# DualMotorCape-v6.net
KiCad netlist of a schematic drawn in EAGLE
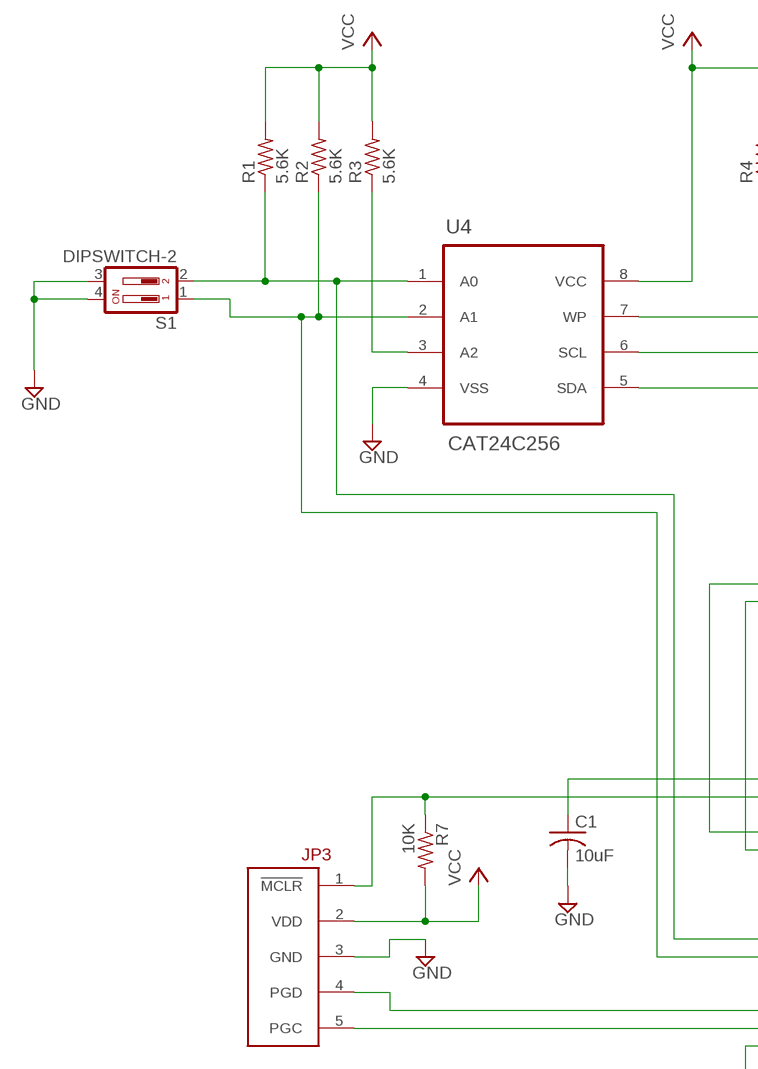
[diagram p0: schematic, sheet 1, part 1 of 2]
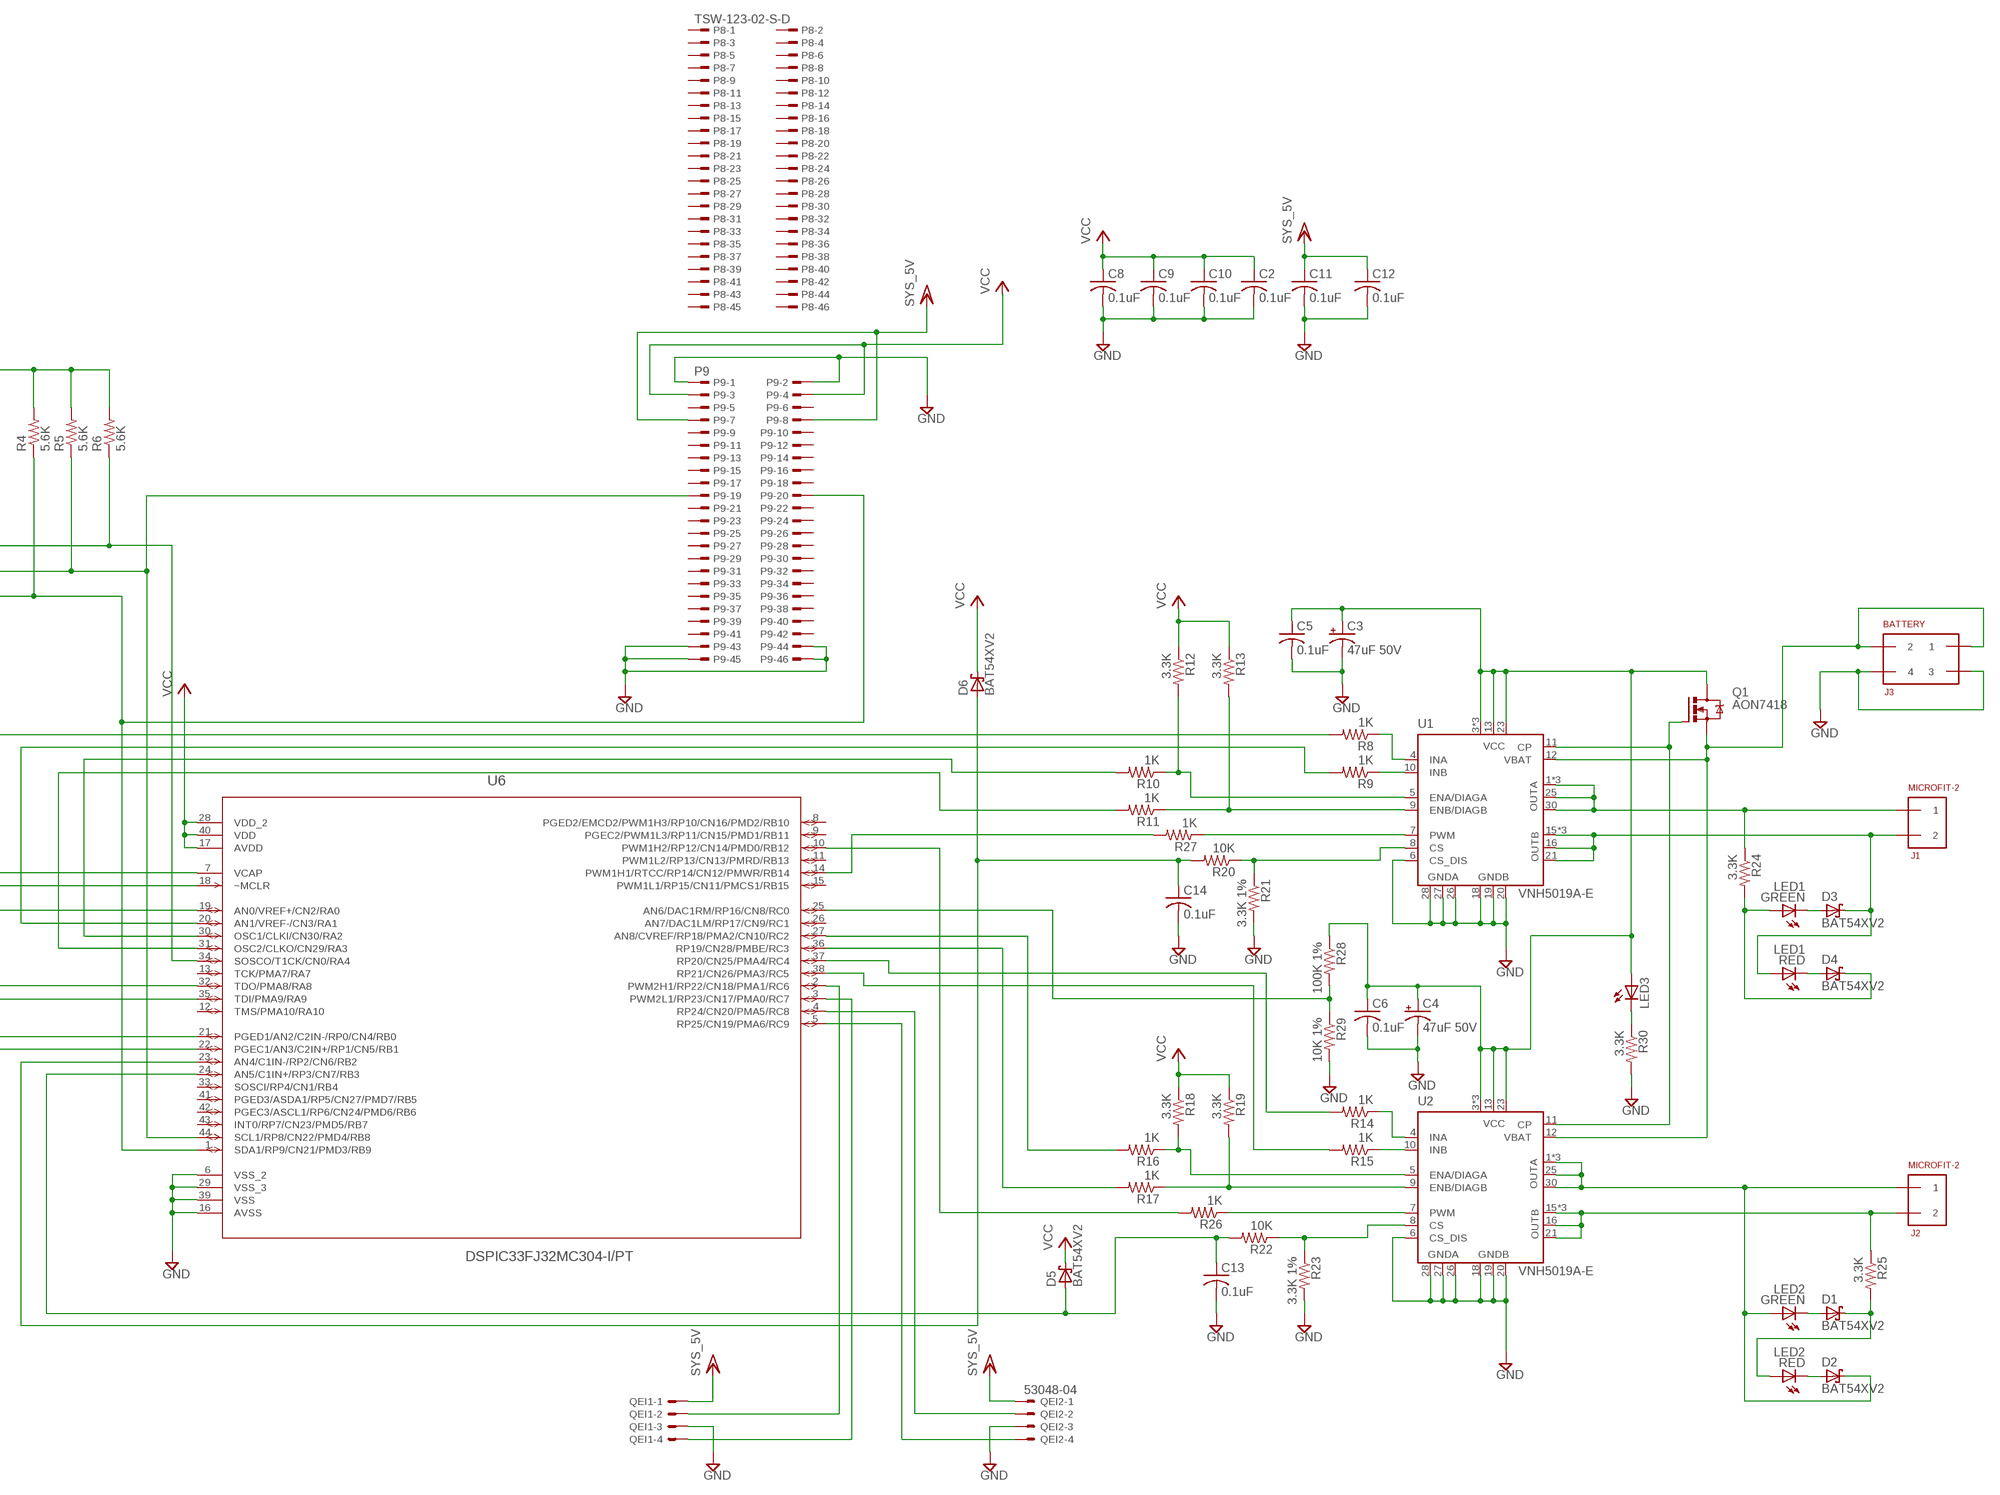
[diagram p1: schematic, sheet 1, part 2 of 2]

(export (version "E")
  (design (tool "Eeschema 10.0.6"))
  (components
    (comp (ref "C1")
      (value "10uF")
      (footprint "eagle-import:C0805")
      (libsource (lib "eagle-import") (part "C-USC0805"))
    )
    (comp (ref "C2")
      (value "0.1uF")
      (footprint "eagle-import:C0603")
      (libsource (lib "eagle-import") (part "C-USC0603"))
    )
    (comp (ref "C3")
      (value "47uF 50V")
      (footprint "eagle-import:UD-8X10_NICHICON")
      (libsource (lib "eagle-import") (part "CPOL-USUD-8X10"))
    )
    (comp (ref "C4")
      (value "47uF 50V")
      (footprint "eagle-import:UD-8X10_NICHICON")
      (libsource (lib "eagle-import") (part "CPOL-USUD-8X10"))
    )
    (comp (ref "C5")
      (value "0.1uF")
      (footprint "eagle-import:C0603")
      (libsource (lib "eagle-import") (part "C-USC0603"))
    )
    (comp (ref "C6")
      (value "0.1uF")
      (footprint "eagle-import:C0603")
      (libsource (lib "eagle-import") (part "C-USC0603"))
    )
    (comp (ref "C8")
      (value "0.1uF")
      (footprint "eagle-import:C0603")
      (libsource (lib "eagle-import") (part "C-USC0603"))
    )
    (comp (ref "C9")
      (value "0.1uF")
      (footprint "eagle-import:C0603")
      (libsource (lib "eagle-import") (part "C-USC0603"))
    )
    (comp (ref "C10")
      (value "0.1uF")
      (footprint "eagle-import:C0603")
      (libsource (lib "eagle-import") (part "C-USC0603"))
    )
    (comp (ref "C11")
      (value "0.1uF")
      (footprint "eagle-import:C0603")
      (libsource (lib "eagle-import") (part "C-USC0603"))
    )
    (comp (ref "C12")
      (value "0.1uF")
      (footprint "eagle-import:C0603")
      (libsource (lib "eagle-import") (part "C-USC0603"))
    )
    (comp (ref "C13")
      (value "0.1uF")
      (footprint "eagle-import:C0603")
      (libsource (lib "eagle-import") (part "C-USC0603"))
    )
    (comp (ref "C14")
      (value "0.1uF")
      (footprint "eagle-import:C0603")
      (libsource (lib "eagle-import") (part "C-USC0603"))
    )
    (comp (ref "D1")
      (value "BAT54XV2")
      (footprint "eagle-import:SOD523")
      (libsource (lib "eagle-import") (part "BAT54XV2"))
    )
    (comp (ref "D2")
      (value "BAT54XV2")
      (footprint "eagle-import:SOD523")
      (libsource (lib "eagle-import") (part "BAT54XV2"))
    )
    (comp (ref "D3")
      (value "BAT54XV2")
      (footprint "eagle-import:SOD523")
      (libsource (lib "eagle-import") (part "BAT54XV2"))
    )
    (comp (ref "D4")
      (value "BAT54XV2")
      (footprint "eagle-import:SOD523")
      (libsource (lib "eagle-import") (part "BAT54XV2"))
    )
    (comp (ref "D5")
      (value "BAT54XV2")
      (footprint "eagle-import:SOD523")
      (libsource (lib "eagle-import") (part "BAT54XV2"))
    )
    (comp (ref "D6")
      (value "BAT54XV2")
      (footprint "eagle-import:SOD523")
      (libsource (lib "eagle-import") (part "BAT54XV2"))
    )
    (comp (ref "J1")
      (value "MICROFIT-2")
      (footprint "eagle-import:MICROFIT-2-R-TH")
      (libsource (lib "eagle-import") (part "MICROFIT-2"))
    )
    (comp (ref "J2")
      (value "MICROFIT-2")
      (footprint "eagle-import:MICROFIT-2-R-TH")
      (libsource (lib "eagle-import") (part "MICROFIT-2"))
    )
    (comp (ref "J3")
      (value "BATTERY")
      (footprint "eagle-import:MICROFIT-4-R-TH")
      (libsource (lib "eagle-import") (part "MICROFIT-4"))
    )
    (comp (ref "JP3")
      (value "ICD2/3-HEADER")
      (footprint "eagle-import:ICD2_3-HEADER")
      (libsource (lib "eagle-import") (part "ICD2/3-HEADER"))
    )
    (comp (ref "LED1")
      (value "KINGBRIGHT-BI-COLOR-LED")
      (footprint "eagle-import:LED-1.6X1.5MM-BI-COLOR")
      (libsource (lib "eagle-import") (part "KINGBRIGHT-BI-COLOR-LED"))
    )
    (comp (ref "LED2")
      (value "KINGBRIGHT-BI-COLOR-LED")
      (footprint "eagle-import:LED-1.6X1.5MM-BI-COLOR")
      (libsource (lib "eagle-import") (part "KINGBRIGHT-BI-COLOR-LED"))
    )
    (comp (ref "LED3")
      (value "LED-LNJP12X8ARA")
      (footprint "eagle-import:LED-603-PANASONIC")
      (libsource (lib "eagle-import") (part "LED-LNJP12X8ARA"))
    )
    (comp (ref "P8")
      (value "TSW-123-02-S-D")
      (footprint "eagle-import:TSW-123-02-S-D")
      (libsource (lib "eagle-import") (part "TSW-123-02-S-D"))
    )
    (comp (ref "P9")
      (value "P9")
      (footprint "eagle-import:TSW-123-02-S-D")
      (libsource (lib "eagle-import") (part "TSW-123-02-S-D"))
    )
    (comp (ref "Q1")
      (value "AON7418")
      (footprint "eagle-import:DFN3.3X3.3")
      (libsource (lib "eagle-import") (part "MOSFET-N"))
    )
    (comp (ref "QEI1")
      (value "53048-04")
      (footprint "eagle-import:53048-04")
      (fields (field (name "MF") "MOLEX") (field (name "MPN") "53048-0410"))
      (libsource (lib "eagle-import") (part "53?-04048"))
    )
    (comp (ref "QEI2")
      (value "53048-04")
      (footprint "eagle-import:53048-04")
      (fields (field (name "MF") "MOLEX") (field (name "MPN") "53048-0410"))
      (libsource (lib "eagle-import") (part "53?-04048"))
    )
    (comp (ref "R1")
      (value "5.6K")
      (footprint "eagle-import:R0603")
      (libsource (lib "eagle-import") (part "R-US_R0603"))
    )
    (comp (ref "R2")
      (value "5.6K")
      (footprint "eagle-import:R0603")
      (libsource (lib "eagle-import") (part "R-US_R0603"))
    )
    (comp (ref "R3")
      (value "5.6K")
      (footprint "eagle-import:R0603")
      (libsource (lib "eagle-import") (part "R-US_R0603"))
    )
    (comp (ref "R4")
      (value "5.6K")
      (footprint "eagle-import:R0603")
      (libsource (lib "eagle-import") (part "R-US_R0603"))
    )
    (comp (ref "R5")
      (value "5.6K")
      (footprint "eagle-import:R0603")
      (libsource (lib "eagle-import") (part "R-US_R0603"))
    )
    (comp (ref "R6")
      (value "5.6K")
      (footprint "eagle-import:R0603")
      (libsource (lib "eagle-import") (part "R-US_R0603"))
    )
    (comp (ref "R7")
      (value "10K")
      (footprint "eagle-import:R0603")
      (libsource (lib "eagle-import") (part "R-US_R0603"))
    )
    (comp (ref "R8")
      (value "1K")
      (footprint "eagle-import:R0603")
      (libsource (lib "eagle-import") (part "R-US_R0603"))
    )
    (comp (ref "R9")
      (value "1K")
      (footprint "eagle-import:R0603")
      (libsource (lib "eagle-import") (part "R-US_R0603"))
    )
    (comp (ref "R10")
      (value "1K")
      (footprint "eagle-import:R0603")
      (libsource (lib "eagle-import") (part "R-US_R0603"))
    )
    (comp (ref "R11")
      (value "1K")
      (footprint "eagle-import:R0603")
      (libsource (lib "eagle-import") (part "R-US_R0603"))
    )
    (comp (ref "R12")
      (value "3.3K")
      (footprint "eagle-import:R0603")
      (libsource (lib "eagle-import") (part "R-US_R0603"))
    )
    (comp (ref "R13")
      (value "3.3K")
      (footprint "eagle-import:R0603")
      (libsource (lib "eagle-import") (part "R-US_R0603"))
    )
    (comp (ref "R14")
      (value "1K")
      (footprint "eagle-import:R0603")
      (libsource (lib "eagle-import") (part "R-US_R0603"))
    )
    (comp (ref "R15")
      (value "1K")
      (footprint "eagle-import:R0603")
      (libsource (lib "eagle-import") (part "R-US_R0603"))
    )
    (comp (ref "R16")
      (value "1K")
      (footprint "eagle-import:R0603")
      (libsource (lib "eagle-import") (part "R-US_R0603"))
    )
    (comp (ref "R17")
      (value "1K")
      (footprint "eagle-import:R0603")
      (libsource (lib "eagle-import") (part "R-US_R0603"))
    )
    (comp (ref "R18")
      (value "3.3K")
      (footprint "eagle-import:R0603")
      (libsource (lib "eagle-import") (part "R-US_R0603"))
    )
    (comp (ref "R19")
      (value "3.3K")
      (footprint "eagle-import:R0603")
      (libsource (lib "eagle-import") (part "R-US_R0603"))
    )
    (comp (ref "R20")
      (value "10K")
      (footprint "eagle-import:R0603")
      (libsource (lib "eagle-import") (part "R-US_R0603"))
    )
    (comp (ref "R21")
      (value "3.3K 1%")
      (footprint "eagle-import:R0603")
      (libsource (lib "eagle-import") (part "R-US_R0603"))
    )
    (comp (ref "R22")
      (value "10K")
      (footprint "eagle-import:R0603")
      (libsource (lib "eagle-import") (part "R-US_R0603"))
    )
    (comp (ref "R23")
      (value "3.3K 1%")
      (footprint "eagle-import:R0603")
      (libsource (lib "eagle-import") (part "R-US_R0603"))
    )
    (comp (ref "R24")
      (value "3.3K")
      (footprint "eagle-import:R0603")
      (libsource (lib "eagle-import") (part "R-US_R0603"))
    )
    (comp (ref "R25")
      (value "3.3K")
      (footprint "eagle-import:R0603")
      (libsource (lib "eagle-import") (part "R-US_R0603"))
    )
    (comp (ref "R26")
      (value "1K")
      (footprint "eagle-import:R0603")
      (libsource (lib "eagle-import") (part "R-US_R0603"))
    )
    (comp (ref "R27")
      (value "1K")
      (footprint "eagle-import:R0603")
      (libsource (lib "eagle-import") (part "R-US_R0603"))
    )
    (comp (ref "R28")
      (value "100K 1%")
      (footprint "eagle-import:R0603")
      (libsource (lib "eagle-import") (part "R-US_R0603"))
    )
    (comp (ref "R29")
      (value "10K 1%")
      (footprint "eagle-import:R0603")
      (libsource (lib "eagle-import") (part "R-US_R0603"))
    )
    (comp (ref "R30")
      (value "3.3K")
      (footprint "eagle-import:R0603")
      (libsource (lib "eagle-import") (part "R-US_R0603"))
    )
    (comp (ref "S1")
      (value "DIPSWITCH-2")
      (footprint "eagle-import:DIPSWITCH-218-2")
      (libsource (lib "eagle-import") (part "DIPSWITCH-2"))
    )
    (comp (ref "U1")
      (value "VNH5019A-E")
      (footprint "eagle-import:VNH5019A-E")
      (libsource (lib "eagle-import") (part "VNH5019A-E"))
    )
    (comp (ref "U2")
      (value "VNH5019A-E")
      (footprint "eagle-import:VNH5019A-E")
      (libsource (lib "eagle-import") (part "VNH5019A-E"))
    )
    (comp (ref "U4")
      (value "CAT24C256")
      (footprint "eagle-import:SOIC-8")
      (libsource (lib "eagle-import") (part "CAT24C256"))
    )
    (comp (ref "U6")
      (value "DSPIC33FJ32MC304-I/PT")
      (footprint "eagle-import:QFP80P1200X1200X120-44N")
      (fields (field (name "MPN") "dspic33fj32mc304-I/pt"))
      (libsource (lib "eagle-import") (part "DSPIC33FJ32MC304-I/PT"))
    )
  )
  (nets
    (net (code "1") (name "GND") (class "Default")
      (node (ref "C1") (pin "2") (pinfunction "2_2") (pintype "passive"))
      (node (ref "C10") (pin "2") (pinfunction "2_2") (pintype "passive"))
      (node (ref "C11") (pin "2") (pinfunction "2_2") (pintype "passive"))
      (node (ref "C12") (pin "2") (pinfunction "2_2") (pintype "passive"))
      (node (ref "C13") (pin "2") (pinfunction "2_2") (pintype "passive"))
      (node (ref "C14") (pin "2") (pinfunction "2_2") (pintype "passive"))
      (node (ref "C2") (pin "2") (pinfunction "2_2") (pintype "passive"))
      (node (ref "C3") (pin "-") (pinfunction "-_-") (pintype "passive"))
      (node (ref "C4") (pin "-") (pinfunction "-_-") (pintype "passive"))
      (node (ref "C5") (pin "2") (pinfunction "2_2") (pintype "passive"))
      (node (ref "C6") (pin "2") (pinfunction "2_2") (pintype "passive"))
      (node (ref "C8") (pin "2") (pinfunction "2_2") (pintype "passive"))
      (node (ref "C9") (pin "2") (pinfunction "2_2") (pintype "passive"))
      (node (ref "J3") (pin "3") (pinfunction "4_3") (pintype "passive"))
      (node (ref "J3") (pin "4") (pinfunction "3_4") (pintype "passive"))
      (node (ref "JP3") (pin "3") (pinfunction "GND_3") (pintype "bidirectional"))
      (node (ref "P9") (pin "1") (pinfunction "1_1") (pintype "passive"))
      (node (ref "P9") (pin "2") (pinfunction "1_2") (pintype "passive"))
      (node (ref "P9") (pin "43") (pinfunction "1_43") (pintype "passive"))
      (node (ref "P9") (pin "44") (pinfunction "1_44") (pintype "passive"))
      (node (ref "P9") (pin "45") (pinfunction "1_45") (pintype "passive"))
      (node (ref "P9") (pin "46") (pinfunction "1_46") (pintype "passive"))
      (node (ref "QEI1") (pin "3") (pinfunction "S_3") (pintype "passive"))
      (node (ref "QEI2") (pin "3") (pinfunction "S_3") (pintype "passive"))
      (node (ref "R21") (pin "2") (pinfunction "2_2") (pintype "passive"))
      (node (ref "R23") (pin "2") (pinfunction "2_2") (pintype "passive"))
      (node (ref "R29") (pin "2") (pinfunction "2_2") (pintype "passive"))
      (node (ref "R30") (pin "2") (pinfunction "2_2") (pintype "passive"))
      (node (ref "S1") (pin "3") (pinfunction "3_3") (pintype "passive"))
      (node (ref "S1") (pin "4") (pinfunction "4_4") (pintype "passive"))
      (node (ref "U1") (pin "18") (pinfunction "GNDB_18") (pintype "power_in"))
      (node (ref "U1") (pin "19") (pinfunction "GNDB_19") (pintype "power_in"))
      (node (ref "U1") (pin "20") (pinfunction "GNDB_20") (pintype "power_in"))
      (node (ref "U1") (pin "26") (pinfunction "GNDA_26") (pintype "power_in"))
      (node (ref "U1") (pin "27") (pinfunction "GNDA_27") (pintype "power_in"))
      (node (ref "U1") (pin "28") (pinfunction "GNDA_28") (pintype "power_in"))
      (node (ref "U1") (pin "6") (pinfunction "CS_DIS_6") (pintype "input"))
      (node (ref "U2") (pin "18") (pinfunction "GNDB_18") (pintype "power_in"))
      (node (ref "U2") (pin "19") (pinfunction "GNDB_19") (pintype "power_in"))
      (node (ref "U2") (pin "20") (pinfunction "GNDB_20") (pintype "power_in"))
      (node (ref "U2") (pin "26") (pinfunction "GNDA_26") (pintype "power_in"))
      (node (ref "U2") (pin "27") (pinfunction "GNDA_27") (pintype "power_in"))
      (node (ref "U2") (pin "28") (pinfunction "GNDA_28") (pintype "power_in"))
      (node (ref "U2") (pin "6") (pinfunction "CS_DIS_6") (pintype "input"))
      (node (ref "U4") (pin "4") (pinfunction "VSS_4") (pintype "power_in"))
      (node (ref "U6") (pin "16") (pinfunction "AVSS_16") (pintype "power_in"))
      (node (ref "U6") (pin "29") (pinfunction "VSS_3_29") (pintype "power_in"))
      (node (ref "U6") (pin "39") (pinfunction "VSS_39") (pintype "power_in"))
      (node (ref "U6") (pin "6") (pinfunction "VSS_2_6") (pintype "power_in"))
    )
    (net (code "2") (name "Net-(D1-PadA)") (class "Default")
      (node (ref "D1") (pin "A") (pinfunction "A_A") (pintype "passive"))
      (node (ref "LED2") (pin "4") (pinfunction "4_4") (pintype "passive"))
    )
    (net (code "3") (name "Net-(D1-PadC)") (class "Default")
      (node (ref "D1") (pin "C") (pinfunction "C_C") (pintype "passive"))
      (node (ref "LED2") (pin "1") (pinfunction "1_1") (pintype "passive"))
      (node (ref "R25") (pin "2") (pinfunction "2_2") (pintype "passive"))
    )
    (net (code "4") (name "Net-(D2-PadA)") (class "Default")
      (node (ref "D2") (pin "A") (pinfunction "A_A") (pintype "passive"))
      (node (ref "LED2") (pin "2") (pinfunction "2_2") (pintype "passive"))
    )
    (net (code "5") (name "Net-(D3-PadA)") (class "Default")
      (node (ref "D3") (pin "A") (pinfunction "A_A") (pintype "passive"))
      (node (ref "LED1") (pin "4") (pinfunction "4_4") (pintype "passive"))
    )
    (net (code "6") (name "Net-(D4-PadA)") (class "Default")
      (node (ref "D4") (pin "A") (pinfunction "A_A") (pintype "passive"))
      (node (ref "LED1") (pin "2") (pinfunction "2_2") (pintype "passive"))
    )
    (net (code "7") (name "Net-(D4-PadC)") (class "Default")
      (node (ref "D4") (pin "C") (pinfunction "C_C") (pintype "passive"))
      (node (ref "LED1") (pin "3") (pinfunction "3_3") (pintype "passive"))
      (node (ref "R24") (pin "2") (pinfunction "2_2") (pintype "passive"))
    )
    (net (code "8") (name "Net-(J1-1)") (class "Default")
      (node (ref "J1") (pin "2") (pinfunction "1_2") (pintype "passive"))
      (node (ref "R24") (pin "1") (pinfunction "1_1") (pintype "passive"))
      (node (ref "U1") (pin "1") (pinfunction "OUTA_1") (pintype "output"))
      (node (ref "U1") (pin "25") (pinfunction "OUTA_25") (pintype "passive"))
      (node (ref "U1") (pin "30") (pinfunction "OUTA_30") (pintype "passive"))
      (node (ref "U1") (pin "NC/OUTA") (pinfunction "OUTA_NC/OUTA") (pintype "output"))
      (node (ref "U1") (pin "NC/OUTA@1") (pinfunction "OUTA_NC/OUTA@1") (pintype "output"))
    )
    (net (code "9") (name "Net-(J1-2)") (class "Default")
      (node (ref "D3") (pin "C") (pinfunction "C_C") (pintype "passive"))
      (node (ref "J1") (pin "1") (pinfunction "2_1") (pintype "passive"))
      (node (ref "LED1") (pin "1") (pinfunction "1_1") (pintype "passive"))
      (node (ref "U1") (pin "15") (pinfunction "OUTB_15") (pintype "output"))
      (node (ref "U1") (pin "16") (pinfunction "OUTB_16") (pintype "passive"))
      (node (ref "U1") (pin "21") (pinfunction "OUTB_21") (pintype "passive"))
      (node (ref "U1") (pin "NC/OUTB") (pinfunction "OUTB_NC/OUTB") (pintype "output"))
      (node (ref "U1") (pin "NC/OUTB@1") (pinfunction "OUTB_NC/OUTB@1") (pintype "output"))
    )
    (net (code "10") (name "Net-(J2-1)") (class "Default")
      (node (ref "D2") (pin "C") (pinfunction "C_C") (pintype "passive"))
      (node (ref "J2") (pin "2") (pinfunction "1_2") (pintype "passive"))
      (node (ref "LED2") (pin "3") (pinfunction "3_3") (pintype "passive"))
      (node (ref "U2") (pin "1") (pinfunction "OUTA_1") (pintype "output"))
      (node (ref "U2") (pin "25") (pinfunction "OUTA_25") (pintype "passive"))
      (node (ref "U2") (pin "30") (pinfunction "OUTA_30") (pintype "passive"))
      (node (ref "U2") (pin "NC/OUTA") (pinfunction "OUTA_NC/OUTA") (pintype "output"))
      (node (ref "U2") (pin "NC/OUTA@1") (pinfunction "OUTA_NC/OUTA@1") (pintype "output"))
    )
    (net (code "11") (name "Net-(J2-2)") (class "Default")
      (node (ref "J2") (pin "1") (pinfunction "2_1") (pintype "passive"))
      (node (ref "R25") (pin "1") (pinfunction "1_1") (pintype "passive"))
      (node (ref "U2") (pin "15") (pinfunction "OUTB_15") (pintype "output"))
      (node (ref "U2") (pin "16") (pinfunction "OUTB_16") (pintype "passive"))
      (node (ref "U2") (pin "21") (pinfunction "OUTB_21") (pintype "passive"))
      (node (ref "U2") (pin "NC/OUTB") (pinfunction "OUTB_NC/OUTB") (pintype "output"))
      (node (ref "U2") (pin "NC/OUTB@1") (pinfunction "OUTB_NC/OUTB@1") (pintype "output"))
    )
    (net (code "12") (name "Net-(J3-1)") (class "Default")
      (node (ref "J3") (pin "1") (pinfunction "2_1") (pintype "passive"))
      (node (ref "J3") (pin "2") (pinfunction "1_2") (pintype "passive"))
      (node (ref "Q1") (pin "1") (pinfunction "S_1") (pintype "passive"))
      (node (ref "Q1") (pin "2") (pinfunction "S_2") (pintype "passive"))
      (node (ref "Q1") (pin "3") (pinfunction "S_3") (pintype "passive"))
      (node (ref "U1") (pin "12") (pinfunction "VBAT_12") (pintype "input"))
      (node (ref "U2") (pin "12") (pinfunction "VBAT_12") (pintype "input"))
    )
    (net (code "13") (name "Net-(JP3-PGC)") (class "Default")
      (node (ref "JP3") (pin "5") (pinfunction "PGC_5") (pintype "bidirectional"))
      (node (ref "U6") (pin "22") (pinfunction "PGEC1/AN3/C2IN+/RP1/CN5/RB1_22") (pintype "bidirectional"))
    )
    (net (code "14") (name "Net-(JP3-PGD)") (class "Default")
      (node (ref "JP3") (pin "4") (pinfunction "PGD_4") (pintype "bidirectional"))
      (node (ref "U6") (pin "21") (pinfunction "PGED1/AN2/C2IN-/RP0/CN4/RB0_21") (pintype "bidirectional"))
    )
    (net (code "15") (name "Net-(JP3-~{MCLR})") (class "Default")
      (node (ref "JP3") (pin "1") (pinfunction "~{MCLR}_1") (pintype "bidirectional"))
      (node (ref "R7") (pin "1") (pinfunction "1_1") (pintype "passive"))
      (node (ref "U6") (pin "18") (pinfunction "~{MCLR}_18") (pintype "input"))
    )
    (net (code "16") (name "Net-(LED3-A)") (class "Default")
      (node (ref "C3") (pin "+") (pinfunction "+_+") (pintype "passive"))
      (node (ref "C4") (pin "+") (pinfunction "+_+") (pintype "passive"))
      (node (ref "C5") (pin "1") (pinfunction "1_1") (pintype "passive"))
      (node (ref "C6") (pin "1") (pinfunction "1_1") (pintype "passive"))
      (node (ref "LED3") (pin "1") (pinfunction "A_1") (pintype "passive"))
      (node (ref "Q1") (pin "5") (pinfunction "D_5") (pintype "passive"))
      (node (ref "Q1") (pin "6") (pinfunction "D_6") (pintype "passive"))
      (node (ref "Q1") (pin "7") (pinfunction "D_7") (pintype "passive"))
      (node (ref "Q1") (pin "8") (pinfunction "D_8") (pintype "passive"))
      (node (ref "Q1") (pin "9") (pinfunction "D_9") (pintype "passive"))
      (node (ref "R28") (pin "1") (pinfunction "1_1") (pintype "passive"))
      (node (ref "U1") (pin "13") (pinfunction "VCC_13") (pintype "power_in"))
      (node (ref "U1") (pin "23") (pinfunction "VCC_23") (pintype "power_in"))
      (node (ref "U1") (pin "3") (pinfunction "VCC_3") (pintype "power_in"))
      (node (ref "U1") (pin "NC/VCC") (pinfunction "VCC_NC/VCC") (pintype "power_in"))
      (node (ref "U1") (pin "NC/VCC@1") (pinfunction "VCC_NC/VCC@1") (pintype "power_in"))
      (node (ref "U2") (pin "13") (pinfunction "VCC_13") (pintype "power_in"))
      (node (ref "U2") (pin "23") (pinfunction "VCC_23") (pintype "power_in"))
      (node (ref "U2") (pin "3") (pinfunction "VCC_3") (pintype "power_in"))
      (node (ref "U2") (pin "NC/VCC") (pinfunction "VCC_NC/VCC") (pintype "power_in"))
      (node (ref "U2") (pin "NC/VCC@1") (pinfunction "VCC_NC/VCC@1") (pintype "power_in"))
    )
    (net (code "17") (name "Net-(LED3-C)") (class "Default")
      (node (ref "LED3") (pin "2") (pinfunction "C_2") (pintype "passive"))
      (node (ref "R30") (pin "1") (pinfunction "1_1") (pintype "passive"))
    )
    (net (code "18") (name "Net-(P9K-1)") (class "Default")
      (node (ref "P9") (pin "19") (pinfunction "1_19") (pintype "passive"))
      (node (ref "R5") (pin "1") (pinfunction "1_1") (pintype "passive"))
      (node (ref "U4") (pin "6") (pinfunction "SCL_6") (pintype "input"))
      (node (ref "U6") (pin "44") (pinfunction "SCL1/RP8/CN22/PMD4/RB8_44") (pintype "bidirectional"))
    )
    (net (code "19") (name "Net-(P9M-1)") (class "Default")
      (node (ref "P9") (pin "20") (pinfunction "1_20") (pintype "passive"))
      (node (ref "R4") (pin "1") (pinfunction "1_1") (pintype "passive"))
      (node (ref "U4") (pin "5") (pinfunction "SDA_5") (pintype "bidirectional"))
      (node (ref "U6") (pin "1") (pinfunction "SDA1/RP9/CN21/PMD3/RB9_1") (pintype "bidirectional"))
    )
    (net (code "20") (name "Net-(Q1-G)") (class "Default")
      (node (ref "Q1") (pin "4") (pinfunction "G_4") (pintype "passive"))
      (node (ref "U1") (pin "11") (pinfunction "CP_11") (pintype "output"))
      (node (ref "U2") (pin "11") (pinfunction "CP_11") (pintype "output"))
    )
    (net (code "21") (name "Net-(QEI1B-S)") (class "Default")
      (node (ref "QEI1") (pin "2") (pinfunction "S_2") (pintype "passive"))
      (node (ref "U6") (pin "2") (pinfunction "PWM2H1/RP22/CN18/PMA1/RC6_2") (pintype "bidirectional"))
    )
    (net (code "22") (name "Net-(QEI1D-S)") (class "Default")
      (node (ref "QEI1") (pin "4") (pinfunction "S_4") (pintype "passive"))
      (node (ref "U6") (pin "3") (pinfunction "PWM2L1/RP23/CN17/PMA0/RC7_3") (pintype "bidirectional"))
    )
    (net (code "23") (name "Net-(QEI2B-S)") (class "Default")
      (node (ref "QEI2") (pin "2") (pinfunction "S_2") (pintype "passive"))
      (node (ref "U6") (pin "4") (pinfunction "RP24/CN20/PMA5/RC8_4") (pintype "bidirectional"))
    )
    (net (code "24") (name "Net-(QEI2D-S)") (class "Default")
      (node (ref "QEI2") (pin "4") (pinfunction "S_4") (pintype "passive"))
      (node (ref "U6") (pin "5") (pinfunction "RP25/CN19/PMA6/RC9_5") (pintype "bidirectional"))
    )
    (net (code "25") (name "Net-(U1-CS)") (class "Default")
      (node (ref "R20") (pin "1") (pinfunction "1_1") (pintype "passive"))
      (node (ref "R21") (pin "1") (pinfunction "1_1") (pintype "passive"))
      (node (ref "U1") (pin "8") (pinfunction "CS_8") (pintype "output"))
    )
    (net (code "26") (name "Net-(U1-ENA{slash}DIAGA)") (class "Default")
      (node (ref "R10") (pin "1") (pinfunction "1_1") (pintype "passive"))
      (node (ref "R12") (pin "2") (pinfunction "2_2") (pintype "passive"))
      (node (ref "U1") (pin "5") (pinfunction "ENA/DIAGA_5") (pintype "open_collector"))
    )
    (net (code "27") (name "Net-(U1-ENB{slash}DIAGB)") (class "Default")
      (node (ref "R11") (pin "1") (pinfunction "1_1") (pintype "passive"))
      (node (ref "R13") (pin "2") (pinfunction "2_2") (pintype "passive"))
      (node (ref "U1") (pin "9") (pinfunction "ENB/DIAGB_9") (pintype "open_collector"))
    )
    (net (code "28") (name "Net-(U1-INA)") (class "Default")
      (node (ref "R8") (pin "1") (pinfunction "1_1") (pintype "passive"))
      (node (ref "U1") (pin "4") (pinfunction "INA_4") (pintype "input"))
    )
    (net (code "29") (name "Net-(U1-INB)") (class "Default")
      (node (ref "R9") (pin "1") (pinfunction "1_1") (pintype "passive"))
      (node (ref "U1") (pin "10") (pinfunction "INB_10") (pintype "input"))
    )
    (net (code "30") (name "Net-(U1-PWM)") (class "Default")
      (node (ref "R27") (pin "1") (pinfunction "1_1") (pintype "passive"))
      (node (ref "U1") (pin "7") (pinfunction "PWM_7") (pintype "input"))
    )
    (net (code "31") (name "Net-(U2-CS)") (class "Default")
      (node (ref "R22") (pin "1") (pinfunction "1_1") (pintype "passive"))
      (node (ref "R23") (pin "1") (pinfunction "1_1") (pintype "passive"))
      (node (ref "U2") (pin "8") (pinfunction "CS_8") (pintype "output"))
    )
    (net (code "32") (name "Net-(U2-ENA{slash}DIAGA)") (class "Default")
      (node (ref "R16") (pin "1") (pinfunction "1_1") (pintype "passive"))
      (node (ref "R18") (pin "2") (pinfunction "2_2") (pintype "passive"))
      (node (ref "U2") (pin "5") (pinfunction "ENA/DIAGA_5") (pintype "open_collector"))
    )
    (net (code "33") (name "Net-(U2-ENB{slash}DIAGB)") (class "Default")
      (node (ref "R17") (pin "1") (pinfunction "1_1") (pintype "passive"))
      (node (ref "R19") (pin "2") (pinfunction "2_2") (pintype "passive"))
      (node (ref "U2") (pin "9") (pinfunction "ENB/DIAGB_9") (pintype "open_collector"))
    )
    (net (code "34") (name "Net-(U2-INA)") (class "Default")
      (node (ref "R14") (pin "1") (pinfunction "1_1") (pintype "passive"))
      (node (ref "U2") (pin "4") (pinfunction "INA_4") (pintype "input"))
    )
    (net (code "35") (name "Net-(U2-INB)") (class "Default")
      (node (ref "R15") (pin "1") (pinfunction "1_1") (pintype "passive"))
      (node (ref "U2") (pin "10") (pinfunction "INB_10") (pintype "input"))
    )
    (net (code "36") (name "Net-(U2-PWM)") (class "Default")
      (node (ref "R26") (pin "1") (pinfunction "1_1") (pintype "passive"))
      (node (ref "U2") (pin "7") (pinfunction "PWM_7") (pintype "input"))
    )
    (net (code "37") (name "Net-(U4-A0)") (class "Default")
      (node (ref "R1") (pin "1") (pinfunction "1_1") (pintype "passive"))
      (node (ref "S1") (pin "2") (pinfunction "2_2") (pintype "passive"))
      (node (ref "U4") (pin "1") (pinfunction "A0_1") (pintype "input"))
      (node (ref "U6") (pin "32") (pinfunction "TDO/PMA8/RA8_32") (pintype "bidirectional"))
    )
    (net (code "38") (name "Net-(U4-A1)") (class "Default")
      (node (ref "R2") (pin "1") (pinfunction "1_1") (pintype "passive"))
      (node (ref "S1") (pin "1") (pinfunction "1_1") (pintype "passive"))
      (node (ref "U4") (pin "2") (pinfunction "A1_2") (pintype "input"))
      (node (ref "U6") (pin "35") (pinfunction "TDI/PMA9/RA9_35") (pintype "bidirectional"))
    )
    (net (code "39") (name "Net-(U4-A2)") (class "Default")
      (node (ref "R3") (pin "1") (pinfunction "1_1") (pintype "passive"))
      (node (ref "U4") (pin "3") (pinfunction "A2_3") (pintype "input"))
    )
    (net (code "40") (name "Net-(U4-WP)") (class "Default")
      (node (ref "R6") (pin "1") (pinfunction "1_1") (pintype "passive"))
      (node (ref "U4") (pin "7") (pinfunction "WP_7") (pintype "input"))
      (node (ref "U6") (pin "34") (pinfunction "SOSCO/T1CK/CN0/RA4_34") (pintype "bidirectional"))
    )
    (net (code "41") (name "Net-(U6-AN0{slash}VREF+{slash}CN2{slash}RA0)") (class "Default")
      (node (ref "R8") (pin "2") (pinfunction "2_2") (pintype "passive"))
      (node (ref "U6") (pin "19") (pinfunction "AN0/VREF+/CN2/RA0_19") (pintype "bidirectional"))
    )
    (net (code "42") (name "Net-(U6-AN1{slash}VREF-{slash}CN3{slash}RA1)") (class "Default")
      (node (ref "R9") (pin "2") (pinfunction "2_2") (pintype "passive"))
      (node (ref "U6") (pin "20") (pinfunction "AN1/VREF-/CN3/RA1_20") (pintype "bidirectional"))
    )
    (net (code "43") (name "Net-(U6-AN4{slash}C1IN-{slash}RP2{slash}CN6{slash}RB2)") (class "Default")
      (node (ref "C14") (pin "1") (pinfunction "1_1") (pintype "passive"))
      (node (ref "D6") (pin "A") (pinfunction "A_A") (pintype "passive"))
      (node (ref "R20") (pin "2") (pinfunction "2_2") (pintype "passive"))
      (node (ref "U6") (pin "23") (pinfunction "AN4/C1IN-/RP2/CN6/RB2_23") (pintype "bidirectional"))
    )
    (net (code "44") (name "Net-(U6-AN5{slash}C1IN+{slash}RP3{slash}CN7{slash}RB3)") (class "Default")
      (node (ref "C13") (pin "1") (pinfunction "1_1") (pintype "passive"))
      (node (ref "D5") (pin "A") (pinfunction "A_A") (pintype "passive"))
      (node (ref "R22") (pin "2") (pinfunction "2_2") (pintype "passive"))
      (node (ref "U6") (pin "24") (pinfunction "AN5/C1IN+/RP3/CN7/RB3_24") (pintype "bidirectional"))
    )
    (net (code "45") (name "Net-(U6-AN6{slash}DAC1RM{slash}RP16{slash}CN8{slash}RC0)") (class "Default")
      (node (ref "R28") (pin "2") (pinfunction "2_2") (pintype "passive"))
      (node (ref "R29") (pin "1") (pinfunction "1_1") (pintype "passive"))
      (node (ref "U6") (pin "25") (pinfunction "AN6/DAC1RM/RP16/CN8/RC0_25") (pintype "bidirectional"))
    )
    (net (code "46") (name "Net-(U6-AN8{slash}CVREF{slash}RP18{slash}PMA2{slash}CN10{slash}RC2)") (class "Default")
      (node (ref "R16") (pin "2") (pinfunction "2_2") (pintype "passive"))
      (node (ref "U6") (pin "27") (pinfunction "AN8/CVREF/RP18/PMA2/CN10/RC2_27") (pintype "bidirectional"))
    )
    (net (code "47") (name "Net-(U6-OSC1{slash}CLKI{slash}CN30{slash}RA2)") (class "Default")
      (node (ref "R10") (pin "2") (pinfunction "2_2") (pintype "passive"))
      (node (ref "U6") (pin "30") (pinfunction "OSC1/CLKI/CN30/RA2_30") (pintype "bidirectional"))
    )
    (net (code "48") (name "Net-(U6-OSC2{slash}CLKO{slash}CN29{slash}RA3)") (class "Default")
      (node (ref "R11") (pin "2") (pinfunction "2_2") (pintype "passive"))
      (node (ref "U6") (pin "31") (pinfunction "OSC2/CLKO/CN29/RA3_31") (pintype "bidirectional"))
    )
    (net (code "49") (name "Net-(U6-PWM1H1{slash}RTCC{slash}RP14{slash}CN12{slash}PMWR{slash}RB14)") (class "Default")
      (node (ref "R27") (pin "2") (pinfunction "2_2") (pintype "passive"))
      (node (ref "U6") (pin "14") (pinfunction "PWM1H1/RTCC/RP14/CN12/PMWR/RB14_14") (pintype "bidirectional"))
    )
    (net (code "50") (name "Net-(U6-PWM1H2{slash}RP12{slash}CN14{slash}PMD0{slash}RB12)") (class "Default")
      (node (ref "R26") (pin "2") (pinfunction "2_2") (pintype "passive"))
      (node (ref "U6") (pin "10") (pinfunction "PWM1H2/RP12/CN14/PMD0/RB12_10") (pintype "bidirectional"))
    )
    (net (code "51") (name "Net-(U6-RP19{slash}CN28{slash}PMBE{slash}RC3)") (class "Default")
      (node (ref "R17") (pin "2") (pinfunction "2_2") (pintype "passive"))
      (node (ref "U6") (pin "36") (pinfunction "RP19/CN28/PMBE/RC3_36") (pintype "bidirectional"))
    )
    (net (code "52") (name "Net-(U6-RP20{slash}CN25{slash}PMA4{slash}RC4)") (class "Default")
      (node (ref "R14") (pin "2") (pinfunction "2_2") (pintype "passive"))
      (node (ref "U6") (pin "37") (pinfunction "RP20/CN25/PMA4/RC4_37") (pintype "bidirectional"))
    )
    (net (code "53") (name "Net-(U6-RP21{slash}CN26{slash}PMA3{slash}RC5)") (class "Default")
      (node (ref "R15") (pin "2") (pinfunction "2_2") (pintype "passive"))
      (node (ref "U6") (pin "38") (pinfunction "RP21/CN26/PMA3/RC5_38") (pintype "bidirectional"))
    )
    (net (code "54") (name "Net-(U6-VCAP)") (class "Default")
      (node (ref "C1") (pin "1") (pinfunction "1_1") (pintype "passive"))
      (node (ref "U6") (pin "7") (pinfunction "VCAP_7") (pintype "power_in"))
    )
    (net (code "55") (name "SYS_5V") (class "Default")
      (node (ref "C11") (pin "1") (pinfunction "1_1") (pintype "passive"))
      (node (ref "C12") (pin "1") (pinfunction "1_1") (pintype "passive"))
      (node (ref "P9") (pin "7") (pinfunction "1_7") (pintype "passive"))
      (node (ref "P9") (pin "8") (pinfunction "1_8") (pintype "passive"))
      (node (ref "QEI1") (pin "1") (pinfunction "S_1") (pintype "passive"))
      (node (ref "QEI2") (pin "1") (pinfunction "S_1") (pintype "passive"))
    )
    (net (code "56") (name "VCC") (class "Default")
      (node (ref "C10") (pin "1") (pinfunction "1_1") (pintype "passive"))
      (node (ref "C2") (pin "1") (pinfunction "1_1") (pintype "passive"))
      (node (ref "C8") (pin "1") (pinfunction "1_1") (pintype "passive"))
      (node (ref "C9") (pin "1") (pinfunction "1_1") (pintype "passive"))
      (node (ref "D5") (pin "C") (pinfunction "C_C") (pintype "passive"))
      (node (ref "D6") (pin "C") (pinfunction "C_C") (pintype "passive"))
      (node (ref "JP3") (pin "2") (pinfunction "VDD_2") (pintype "bidirectional"))
      (node (ref "P9") (pin "3") (pinfunction "1_3") (pintype "passive"))
      (node (ref "P9") (pin "4") (pinfunction "1_4") (pintype "passive"))
      (node (ref "R1") (pin "2") (pinfunction "2_2") (pintype "passive"))
      (node (ref "R12") (pin "1") (pinfunction "1_1") (pintype "passive"))
      (node (ref "R13") (pin "1") (pinfunction "1_1") (pintype "passive"))
      (node (ref "R18") (pin "1") (pinfunction "1_1") (pintype "passive"))
      (node (ref "R19") (pin "1") (pinfunction "1_1") (pintype "passive"))
      (node (ref "R2") (pin "2") (pinfunction "2_2") (pintype "passive"))
      (node (ref "R3") (pin "2") (pinfunction "2_2") (pintype "passive"))
      (node (ref "R4") (pin "2") (pinfunction "2_2") (pintype "passive"))
      (node (ref "R5") (pin "2") (pinfunction "2_2") (pintype "passive"))
      (node (ref "R6") (pin "2") (pinfunction "2_2") (pintype "passive"))
      (node (ref "R7") (pin "2") (pinfunction "2_2") (pintype "passive"))
      (node (ref "U4") (pin "8") (pinfunction "VCC_8") (pintype "power_in"))
      (node (ref "U6") (pin "17") (pinfunction "AVDD_17") (pintype "power_in"))
      (node (ref "U6") (pin "28") (pinfunction "VDD_2_28") (pintype "power_in"))
      (node (ref "U6") (pin "40") (pinfunction "VDD_40") (pintype "power_in"))
    )
    (net (code "57") (name "unconnected-(P8-Pad1)") (class "Default")
      (node (ref "P8") (pin "1") (pinfunction "1_1") (pintype "passive"))
    )
    (net (code "58") (name "unconnected-(P8AA-1-Pad33)") (class "Default")
      (node (ref "P8") (pin "33") (pinfunction "1_33") (pintype "passive"))
    )
    (net (code "59") (name "unconnected-(P8AB-1-Pad34)") (class "Default")
      (node (ref "P8") (pin "34") (pinfunction "1_34") (pintype "passive"))
    )
    (net (code "60") (name "unconnected-(P8AC-1-Pad35)") (class "Default")
      (node (ref "P8") (pin "35") (pinfunction "1_35") (pintype "passive"))
    )
    (net (code "61") (name "unconnected-(P8AD-1-Pad36)") (class "Default")
      (node (ref "P8") (pin "36") (pinfunction "1_36") (pintype "passive"))
    )
    (net (code "62") (name "unconnected-(P8AE-1-Pad37)") (class "Default")
      (node (ref "P8") (pin "37") (pinfunction "1_37") (pintype "passive"))
    )
    (net (code "63") (name "unconnected-(P8AF-1-Pad38)") (class "Default")
      (node (ref "P8") (pin "38") (pinfunction "1_38") (pintype "passive"))
    )
    (net (code "64") (name "unconnected-(P8AG-1-Pad39)") (class "Default")
      (node (ref "P8") (pin "39") (pinfunction "1_39") (pintype "passive"))
    )
    (net (code "65") (name "unconnected-(P8AH-1-Pad4)") (class "Default")
      (node (ref "P8") (pin "4") (pinfunction "1_4") (pintype "passive"))
    )
    (net (code "66") (name "unconnected-(P8AI-1-Pad40)") (class "Default")
      (node (ref "P8") (pin "40") (pinfunction "1_40") (pintype "passive"))
    )
    (net (code "67") (name "unconnected-(P8AJ-1-Pad41)") (class "Default")
      (node (ref "P8") (pin "41") (pinfunction "1_41") (pintype "passive"))
    )
    (net (code "68") (name "unconnected-(P8AK-1-Pad42)") (class "Default")
      (node (ref "P8") (pin "42") (pinfunction "1_42") (pintype "passive"))
    )
    (net (code "69") (name "unconnected-(P8AL-1-Pad43)") (class "Default")
      (node (ref "P8") (pin "43") (pinfunction "1_43") (pintype "passive"))
    )
    (net (code "70") (name "unconnected-(P8AM-1-Pad44)") (class "Default")
      (node (ref "P8") (pin "44") (pinfunction "1_44") (pintype "passive"))
    )
    (net (code "71") (name "unconnected-(P8AN-1-Pad45)") (class "Default")
      (node (ref "P8") (pin "45") (pinfunction "1_45") (pintype "passive"))
    )
    (net (code "72") (name "unconnected-(P8AO-1-Pad46)") (class "Default")
      (node (ref "P8") (pin "46") (pinfunction "1_46") (pintype "passive"))
    )
    (net (code "73") (name "unconnected-(P8AP-1-Pad5)") (class "Default")
      (node (ref "P8") (pin "5") (pinfunction "1_5") (pintype "passive"))
    )
    (net (code "74") (name "unconnected-(P8AQ-1-Pad6)") (class "Default")
      (node (ref "P8") (pin "6") (pinfunction "1_6") (pintype "passive"))
    )
    (net (code "75") (name "unconnected-(P8AR-1-Pad7)") (class "Default")
      (node (ref "P8") (pin "7") (pinfunction "1_7") (pintype "passive"))
    )
    (net (code "76") (name "unconnected-(P8AS-1-Pad8)") (class "Default")
      (node (ref "P8") (pin "8") (pinfunction "1_8") (pintype "passive"))
    )
    (net (code "77") (name "unconnected-(P8AT-1-Pad9)") (class "Default")
      (node (ref "P8") (pin "9") (pinfunction "1_9") (pintype "passive"))
    )
    (net (code "78") (name "unconnected-(P8B-1-Pad10)") (class "Default")
      (node (ref "P8") (pin "10") (pinfunction "1_10") (pintype "passive"))
    )
    (net (code "79") (name "unconnected-(P8C-1-Pad11)") (class "Default")
      (node (ref "P8") (pin "11") (pinfunction "1_11") (pintype "passive"))
    )
    (net (code "80") (name "unconnected-(P8D-1-Pad12)") (class "Default")
      (node (ref "P8") (pin "12") (pinfunction "1_12") (pintype "passive"))
    )
    (net (code "81") (name "unconnected-(P8E-1-Pad13)") (class "Default")
      (node (ref "P8") (pin "13") (pinfunction "1_13") (pintype "passive"))
    )
    (net (code "82") (name "unconnected-(P8F-1-Pad14)") (class "Default")
      (node (ref "P8") (pin "14") (pinfunction "1_14") (pintype "passive"))
    )
    (net (code "83") (name "unconnected-(P8G-1-Pad15)") (class "Default")
      (node (ref "P8") (pin "15") (pinfunction "1_15") (pintype "passive"))
    )
    (net (code "84") (name "unconnected-(P8H-1-Pad16)") (class "Default")
      (node (ref "P8") (pin "16") (pinfunction "1_16") (pintype "passive"))
    )
    (net (code "85") (name "unconnected-(P8I-1-Pad17)") (class "Default")
      (node (ref "P8") (pin "17") (pinfunction "1_17") (pintype "passive"))
    )
    (net (code "86") (name "unconnected-(P8J-1-Pad18)") (class "Default")
      (node (ref "P8") (pin "18") (pinfunction "1_18") (pintype "passive"))
    )
    (net (code "87") (name "unconnected-(P8K-1-Pad19)") (class "Default")
      (node (ref "P8") (pin "19") (pinfunction "1_19") (pintype "passive"))
    )
    (net (code "88") (name "unconnected-(P8L-1-Pad2)") (class "Default")
      (node (ref "P8") (pin "2") (pinfunction "1_2") (pintype "passive"))
    )
    (net (code "89") (name "unconnected-(P8M-1-Pad20)") (class "Default")
      (node (ref "P8") (pin "20") (pinfunction "1_20") (pintype "passive"))
    )
    (net (code "90") (name "unconnected-(P8N-1-Pad21)") (class "Default")
      (node (ref "P8") (pin "21") (pinfunction "1_21") (pintype "passive"))
    )
    (net (code "91") (name "unconnected-(P8O-1-Pad22)") (class "Default")
      (node (ref "P8") (pin "22") (pinfunction "1_22") (pintype "passive"))
    )
    (net (code "92") (name "unconnected-(P8P-1-Pad23)") (class "Default")
      (node (ref "P8") (pin "23") (pinfunction "1_23") (pintype "passive"))
    )
    (net (code "93") (name "unconnected-(P8Q-1-Pad24)") (class "Default")
      (node (ref "P8") (pin "24") (pinfunction "1_24") (pintype "passive"))
    )
    (net (code "94") (name "unconnected-(P8R-1-Pad25)") (class "Default")
      (node (ref "P8") (pin "25") (pinfunction "1_25") (pintype "passive"))
    )
    (net (code "95") (name "unconnected-(P8S-1-Pad26)") (class "Default")
      (node (ref "P8") (pin "26") (pinfunction "1_26") (pintype "passive"))
    )
    (net (code "96") (name "unconnected-(P8T-1-Pad27)") (class "Default")
      (node (ref "P8") (pin "27") (pinfunction "1_27") (pintype "passive"))
    )
    (net (code "97") (name "unconnected-(P8U-1-Pad28)") (class "Default")
      (node (ref "P8") (pin "28") (pinfunction "1_28") (pintype "passive"))
    )
    (net (code "98") (name "unconnected-(P8V-1-Pad29)") (class "Default")
      (node (ref "P8") (pin "29") (pinfunction "1_29") (pintype "passive"))
    )
    (net (code "99") (name "unconnected-(P8W-1-Pad3)") (class "Default")
      (node (ref "P8") (pin "3") (pinfunction "1_3") (pintype "passive"))
    )
    (net (code "100") (name "unconnected-(P8X-1-Pad30)") (class "Default")
      (node (ref "P8") (pin "30") (pinfunction "1_30") (pintype "passive"))
    )
    (net (code "101") (name "unconnected-(P8Y-1-Pad31)") (class "Default")
      (node (ref "P8") (pin "31") (pinfunction "1_31") (pintype "passive"))
    )
    (net (code "102") (name "unconnected-(P8Z-1-Pad32)") (class "Default")
      (node (ref "P8") (pin "32") (pinfunction "1_32") (pintype "passive"))
    )
    (net (code "103") (name "unconnected-(P9AA-1-Pad33)") (class "Default")
      (node (ref "P9") (pin "33") (pinfunction "1_33") (pintype "passive"))
    )
    (net (code "104") (name "unconnected-(P9AB-1-Pad34)") (class "Default")
      (node (ref "P9") (pin "34") (pinfunction "1_34") (pintype "passive"))
    )
    (net (code "105") (name "unconnected-(P9AC-1-Pad35)") (class "Default")
      (node (ref "P9") (pin "35") (pinfunction "1_35") (pintype "passive"))
    )
    (net (code "106") (name "unconnected-(P9AD-1-Pad36)") (class "Default")
      (node (ref "P9") (pin "36") (pinfunction "1_36") (pintype "passive"))
    )
    (net (code "107") (name "unconnected-(P9AE-1-Pad37)") (class "Default")
      (node (ref "P9") (pin "37") (pinfunction "1_37") (pintype "passive"))
    )
    (net (code "108") (name "unconnected-(P9AF-1-Pad38)") (class "Default")
      (node (ref "P9") (pin "38") (pinfunction "1_38") (pintype "passive"))
    )
    (net (code "109") (name "unconnected-(P9AG-1-Pad39)") (class "Default")
      (node (ref "P9") (pin "39") (pinfunction "1_39") (pintype "passive"))
    )
    (net (code "110") (name "unconnected-(P9AI-1-Pad40)") (class "Default")
      (node (ref "P9") (pin "40") (pinfunction "1_40") (pintype "passive"))
    )
    (net (code "111") (name "unconnected-(P9AJ-1-Pad41)") (class "Default")
      (node (ref "P9") (pin "41") (pinfunction "1_41") (pintype "passive"))
    )
    (net (code "112") (name "unconnected-(P9AK-1-Pad42)") (class "Default")
      (node (ref "P9") (pin "42") (pinfunction "1_42") (pintype "passive"))
    )
    (net (code "113") (name "unconnected-(P9AP-1-Pad5)") (class "Default")
      (node (ref "P9") (pin "5") (pinfunction "1_5") (pintype "passive"))
    )
    (net (code "114") (name "unconnected-(P9AQ-1-Pad6)") (class "Default")
      (node (ref "P9") (pin "6") (pinfunction "1_6") (pintype "passive"))
    )
    (net (code "115") (name "unconnected-(P9AT-1-Pad9)") (class "Default")
      (node (ref "P9") (pin "9") (pinfunction "1_9") (pintype "passive"))
    )
    (net (code "116") (name "unconnected-(P9B-1-Pad10)") (class "Default")
      (node (ref "P9") (pin "10") (pinfunction "1_10") (pintype "passive"))
    )
    (net (code "117") (name "unconnected-(P9C-1-Pad11)") (class "Default")
      (node (ref "P9") (pin "11") (pinfunction "1_11") (pintype "passive"))
    )
    (net (code "118") (name "unconnected-(P9D-1-Pad12)") (class "Default")
      (node (ref "P9") (pin "12") (pinfunction "1_12") (pintype "passive"))
    )
    (net (code "119") (name "unconnected-(P9E-1-Pad13)") (class "Default")
      (node (ref "P9") (pin "13") (pinfunction "1_13") (pintype "passive"))
    )
    (net (code "120") (name "unconnected-(P9F-1-Pad14)") (class "Default")
      (node (ref "P9") (pin "14") (pinfunction "1_14") (pintype "passive"))
    )
    (net (code "121") (name "unconnected-(P9G-1-Pad15)") (class "Default")
      (node (ref "P9") (pin "15") (pinfunction "1_15") (pintype "passive"))
    )
    (net (code "122") (name "unconnected-(P9H-1-Pad16)") (class "Default")
      (node (ref "P9") (pin "16") (pinfunction "1_16") (pintype "passive"))
    )
    (net (code "123") (name "unconnected-(P9I-1-Pad17)") (class "Default")
      (node (ref "P9") (pin "17") (pinfunction "1_17") (pintype "passive"))
    )
    (net (code "124") (name "unconnected-(P9J-1-Pad18)") (class "Default")
      (node (ref "P9") (pin "18") (pinfunction "1_18") (pintype "passive"))
    )
    (net (code "125") (name "unconnected-(P9N-1-Pad21)") (class "Default")
      (node (ref "P9") (pin "21") (pinfunction "1_21") (pintype "passive"))
    )
    (net (code "126") (name "unconnected-(P9O-1-Pad22)") (class "Default")
      (node (ref "P9") (pin "22") (pinfunction "1_22") (pintype "passive"))
    )
    (net (code "127") (name "unconnected-(P9P-1-Pad23)") (class "Default")
      (node (ref "P9") (pin "23") (pinfunction "1_23") (pintype "passive"))
    )
    (net (code "128") (name "unconnected-(P9Q-1-Pad24)") (class "Default")
      (node (ref "P9") (pin "24") (pinfunction "1_24") (pintype "passive"))
    )
    (net (code "129") (name "unconnected-(P9R-1-Pad25)") (class "Default")
      (node (ref "P9") (pin "25") (pinfunction "1_25") (pintype "passive"))
    )
    (net (code "130") (name "unconnected-(P9S-1-Pad26)") (class "Default")
      (node (ref "P9") (pin "26") (pinfunction "1_26") (pintype "passive"))
    )
    (net (code "131") (name "unconnected-(P9T-1-Pad27)") (class "Default")
      (node (ref "P9") (pin "27") (pinfunction "1_27") (pintype "passive"))
    )
    (net (code "132") (name "unconnected-(P9U-1-Pad28)") (class "Default")
      (node (ref "P9") (pin "28") (pinfunction "1_28") (pintype "passive"))
    )
    (net (code "133") (name "unconnected-(P9V-1-Pad29)") (class "Default")
      (node (ref "P9") (pin "29") (pinfunction "1_29") (pintype "passive"))
    )
    (net (code "134") (name "unconnected-(P9X-1-Pad30)") (class "Default")
      (node (ref "P9") (pin "30") (pinfunction "1_30") (pintype "passive"))
    )
    (net (code "135") (name "unconnected-(P9Y-1-Pad31)") (class "Default")
      (node (ref "P9") (pin "31") (pinfunction "1_31") (pintype "passive"))
    )
    (net (code "136") (name "unconnected-(P9Z-1-Pad32)") (class "Default")
      (node (ref "P9") (pin "32") (pinfunction "1_32") (pintype "passive"))
    )
    (net (code "137") (name "unconnected-(U6-AN7{slash}DAC1LM{slash}RP17{slash}CN9{slash}RC1-Pad26)") (class "Default")
      (node (ref "U6") (pin "26") (pinfunction "AN7/DAC1LM/RP17/CN9/RC1_26") (pintype "bidirectional"))
    )
    (net (code "138") (name "unconnected-(U6-INT0{slash}RP7{slash}CN23{slash}PMD5{slash}RB7-Pad43)") (class "Default")
      (node (ref "U6") (pin "43") (pinfunction "INT0/RP7/CN23/PMD5/RB7_43") (pintype "bidirectional"))
    )
    (net (code "139") (name "unconnected-(U6-PGEC2{slash}PWM1L3{slash}RP11{slash}CN15{slash}PMD1{slash}RB11-Pad9)") (class "Default")
      (node (ref "U6") (pin "9") (pinfunction "PGEC2/PWM1L3/RP11/CN15/PMD1/RB11_9") (pintype "bidirectional"))
    )
    (net (code "140") (name "unconnected-(U6-PGEC3{slash}ASCL1{slash}RP6{slash}CN24{slash}PMD6{slash}RB6-Pad42)") (class "Default")
      (node (ref "U6") (pin "42") (pinfunction "PGEC3/ASCL1/RP6/CN24/PMD6/RB6_42") (pintype "bidirectional"))
    )
    (net (code "141") (name "unconnected-(U6-PGED2{slash}EMCD2{slash}PWM1H3{slash}RP10{slash}CN16{slash}PMD2{slash}RB10-Pad8)") (class "Default")
      (node (ref "U6") (pin "8") (pinfunction "PGED2/EMCD2/PWM1H3/RP10/CN16/PMD2/RB10_8") (pintype "bidirectional"))
    )
    (net (code "142") (name "unconnected-(U6-PGED3{slash}ASDA1{slash}RP5{slash}CN27{slash}PMD7{slash}RB5-Pad41)") (class "Default")
      (node (ref "U6") (pin "41") (pinfunction "PGED3/ASDA1/RP5/CN27/PMD7/RB5_41") (pintype "bidirectional"))
    )
    (net (code "143") (name "unconnected-(U6-PWM1L1{slash}RP15{slash}CN11{slash}PMCS1{slash}RB15-Pad15)") (class "Default")
      (node (ref "U6") (pin "15") (pinfunction "PWM1L1/RP15/CN11/PMCS1/RB15_15") (pintype "bidirectional"))
    )
    (net (code "144") (name "unconnected-(U6-PWM1L2{slash}RP13{slash}CN13{slash}PMRD{slash}RB13-Pad11)") (class "Default")
      (node (ref "U6") (pin "11") (pinfunction "PWM1L2/RP13/CN13/PMRD/RB13_11") (pintype "bidirectional"))
    )
    (net (code "145") (name "unconnected-(U6-SOSCI{slash}RP4{slash}CN1{slash}RB4-Pad33)") (class "Default")
      (node (ref "U6") (pin "33") (pinfunction "SOSCI/RP4/CN1/RB4_33") (pintype "bidirectional"))
    )
    (net (code "146") (name "unconnected-(U6-TCK{slash}PMA7{slash}RA7-Pad13)") (class "Default")
      (node (ref "U6") (pin "13") (pinfunction "TCK/PMA7/RA7_13") (pintype "bidirectional"))
    )
    (net (code "147") (name "unconnected-(U6-TMS{slash}PMA10{slash}RA10-Pad12)") (class "Default")
      (node (ref "U6") (pin "12") (pinfunction "TMS/PMA10/RA10_12") (pintype "bidirectional"))
    )
  )
)
